# ContunityTestingRig.net
KiCad netlist of a schematic drawn in EAGLE
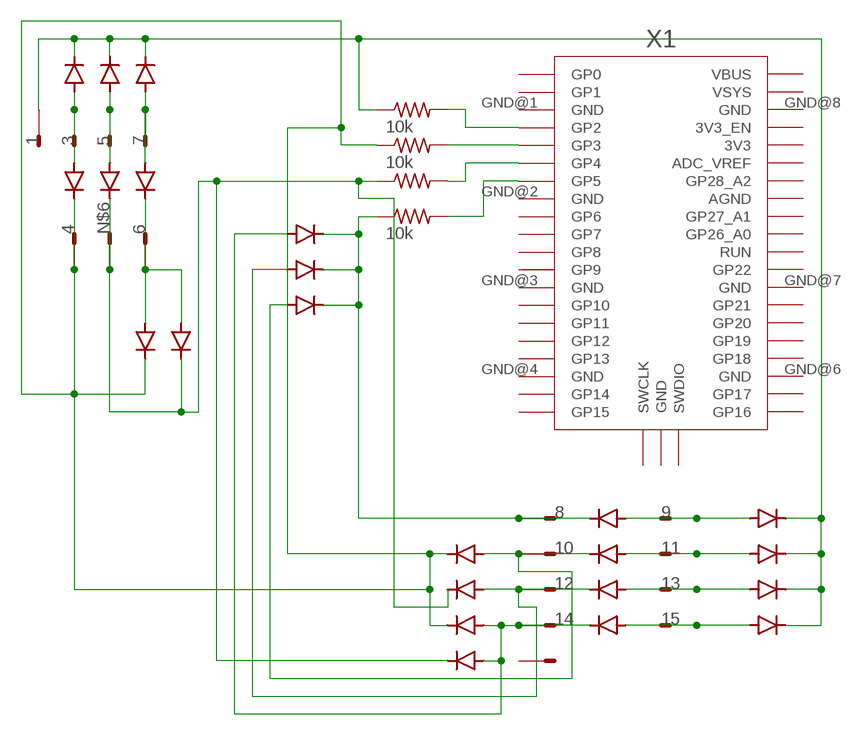
[diagram p0: schematic, sheet 1]

(export (version "E")
  (design (tool "Eeschema 10.0.6"))
  (components
    (comp (ref "D1")
      (value "SCHOTTKY")
      (footprint "eagle-import:MINI-SMA")
      (libsource (lib "eagle-import") (part "DIODE_SCHOTTKY_CDBM1100-G"))
    )
    (comp (ref "D2")
      (value "SCHOTTKY")
      (footprint "eagle-import:MINI-SMA")
      (libsource (lib "eagle-import") (part "DIODE_SCHOTTKY_CDBM1100-G"))
    )
    (comp (ref "D3")
      (value "SCHOTTKY")
      (footprint "eagle-import:MINI-SMA")
      (libsource (lib "eagle-import") (part "DIODE_SCHOTTKY_CDBM1100-G"))
    )
    (comp (ref "D4")
      (value "SCHOTTKY")
      (footprint "eagle-import:MINI-SMA")
      (libsource (lib "eagle-import") (part "DIODE_SCHOTTKY_CDBM1100-G"))
    )
    (comp (ref "D5")
      (value "SCHOTTKY")
      (footprint "eagle-import:MINI-SMA")
      (libsource (lib "eagle-import") (part "DIODE_SCHOTTKY_CDBM1100-G"))
    )
    (comp (ref "D6")
      (value "SCHOTTKY")
      (footprint "eagle-import:MINI-SMA")
      (libsource (lib "eagle-import") (part "DIODE_SCHOTTKY_CDBM1100-G"))
    )
    (comp (ref "D7")
      (value "SCHOTTKY")
      (footprint "eagle-import:MINI-SMA")
      (libsource (lib "eagle-import") (part "DIODE_SCHOTTKY_CDBM1100-G"))
    )
    (comp (ref "D8")
      (value "SCHOTTKY")
      (footprint "eagle-import:MINI-SMA")
      (libsource (lib "eagle-import") (part "DIODE_SCHOTTKY_CDBM1100-G"))
    )
    (comp (ref "D9")
      (value "SCHOTTKY")
      (footprint "eagle-import:MINI-SMA")
      (libsource (lib "eagle-import") (part "DIODE_SCHOTTKY_CDBM1100-G"))
    )
    (comp (ref "D10")
      (value "SCHOTTKY")
      (footprint "eagle-import:MINI-SMA")
      (libsource (lib "eagle-import") (part "DIODE_SCHOTTKY_CDBM1100-G"))
    )
    (comp (ref "D11")
      (value "SCHOTTKY")
      (footprint "eagle-import:MINI-SMA")
      (libsource (lib "eagle-import") (part "DIODE_SCHOTTKY_CDBM1100-G"))
    )
    (comp (ref "D12")
      (value "SCHOTTKY")
      (footprint "eagle-import:MINI-SMA")
      (libsource (lib "eagle-import") (part "DIODE_SCHOTTKY_CDBM1100-G"))
    )
    (comp (ref "D13")
      (value "SCHOTTKY")
      (footprint "eagle-import:MINI-SMA")
      (libsource (lib "eagle-import") (part "DIODE_SCHOTTKY_CDBM1100-G"))
    )
    (comp (ref "D14")
      (value "SCHOTTKY")
      (footprint "eagle-import:MINI-SMA")
      (libsource (lib "eagle-import") (part "DIODE_SCHOTTKY_CDBM1100-G"))
    )
    (comp (ref "D15")
      (value "SCHOTTKY")
      (footprint "eagle-import:MINI-SMA")
      (libsource (lib "eagle-import") (part "DIODE_SCHOTTKY_CDBM1100-G"))
    )
    (comp (ref "D16")
      (value "SCHOTTKY")
      (footprint "eagle-import:MINI-SMA")
      (libsource (lib "eagle-import") (part "DIODE_SCHOTTKY_CDBM1100-G"))
    )
    (comp (ref "D17")
      (value "SCHOTTKY")
      (footprint "eagle-import:MINI-SMA")
      (libsource (lib "eagle-import") (part "DIODE_SCHOTTKY_CDBM1100-G"))
    )
    (comp (ref "D18")
      (value "SCHOTTKY")
      (footprint "eagle-import:MINI-SMA")
      (libsource (lib "eagle-import") (part "DIODE_SCHOTTKY_CDBM1100-G"))
    )
    (comp (ref "D19")
      (value "SCHOTTKY")
      (footprint "eagle-import:MINI-SMA")
      (libsource (lib "eagle-import") (part "DIODE_SCHOTTKY_CDBM1100-G"))
    )
    (comp (ref "D20")
      (value "SCHOTTKY")
      (footprint "eagle-import:MINI-SMA")
      (libsource (lib "eagle-import") (part "DIODE_SCHOTTKY_CDBM1100-G"))
    )
    (comp (ref "D21")
      (value "SCHOTTKY")
      (footprint "eagle-import:MINI-SMA")
      (libsource (lib "eagle-import") (part "DIODE_SCHOTTKY_CDBM1100-G"))
    )
    (comp (ref "D22")
      (value "SCHOTTKY")
      (footprint "eagle-import:MINI-SMA")
      (libsource (lib "eagle-import") (part "DIODE_SCHOTTKY_CDBM1100-G"))
    )
    (comp (ref "D23")
      (value "SCHOTTKY")
      (footprint "eagle-import:MINI-SMA")
      (libsource (lib "eagle-import") (part "DIODE_SCHOTTKY_CDBM1100-G"))
    )
    (comp (ref "R1")
      (value "10k")
      (footprint "eagle-import:R1206FAB")
      (libsource (lib "eagle-import") (part "R1206FAB"))
    )
    (comp (ref "R2")
      (value "10k")
      (footprint "eagle-import:R1206FAB")
      (libsource (lib "eagle-import") (part "R1206FAB"))
    )
    (comp (ref "R3")
      (value "10k")
      (footprint "eagle-import:R1206FAB")
      (libsource (lib "eagle-import") (part "R1206FAB"))
    )
    (comp (ref "R4")
      (value "10k")
      (footprint "eagle-import:R1206FAB")
      (libsource (lib "eagle-import") (part "R1206FAB"))
    )
    (comp (ref "SV1")
      (value "16E")
      (footprint "eagle-import:16P")
      (libsource (lib "eagle-import") (part "16E"))
    )
    (comp (ref "X1")
      (value "RPI_PICO_IG-SMD")
      (footprint "eagle-import:RPI_PICO")
      (libsource (lib "eagle-import") (part "RPI_PICO_IG-SMD"))
    )
  )
  (nets
    (net (code "1") (name "/1") (class "Default")
      (node (ref "D1") (pin "KATHODE") (pinfunction "KATHODE_KATHODE") (pintype "bidirectional"))
      (node (ref "D13") (pin "KATHODE") (pinfunction "KATHODE_KATHODE") (pintype "bidirectional"))
      (node (ref "D14") (pin "KATHODE") (pinfunction "KATHODE_KATHODE") (pintype "bidirectional"))
      (node (ref "D15") (pin "KATHODE") (pinfunction "KATHODE_KATHODE") (pintype "bidirectional"))
      (node (ref "D16") (pin "KATHODE") (pinfunction "KATHODE_KATHODE") (pintype "bidirectional"))
      (node (ref "D2") (pin "KATHODE") (pinfunction "KATHODE_KATHODE") (pintype "bidirectional"))
      (node (ref "D3") (pin "KATHODE") (pinfunction "KATHODE_KATHODE") (pintype "bidirectional"))
      (node (ref "R1") (pin "1") (pinfunction "1_1") (pintype "passive"))
      (node (ref "SV1") (pin "1") (pinfunction "S_1") (pintype "passive"))
    )
    (net (code "2") (name "/3") (class "Default")
      (node (ref "D1") (pin "ANODE") (pinfunction "ANODE_ANODE") (pintype "bidirectional"))
      (node (ref "D4") (pin "ANODE") (pinfunction "ANODE_ANODE") (pintype "bidirectional"))
      (node (ref "SV1") (pin "3") (pinfunction "S_3") (pintype "passive"))
    )
    (net (code "3") (name "/4") (class "Default")
      (node (ref "D17") (pin "KATHODE") (pinfunction "KATHODE_KATHODE") (pintype "bidirectional"))
      (node (ref "D18") (pin "KATHODE") (pinfunction "KATHODE_KATHODE") (pintype "bidirectional"))
      (node (ref "D4") (pin "KATHODE") (pinfunction "KATHODE_KATHODE") (pintype "bidirectional"))
      (node (ref "D7") (pin "KATHODE") (pinfunction "KATHODE_KATHODE") (pintype "bidirectional"))
      (node (ref "R2") (pin "1") (pinfunction "1_1") (pintype "passive"))
      (node (ref "SV1") (pin "2") (pinfunction "S_2") (pintype "passive"))
    )
    (net (code "4") (name "/5") (class "Default")
      (node (ref "D2") (pin "ANODE") (pinfunction "ANODE_ANODE") (pintype "bidirectional"))
      (node (ref "D5") (pin "ANODE") (pinfunction "ANODE_ANODE") (pintype "bidirectional"))
      (node (ref "SV1") (pin "5") (pinfunction "S_5") (pintype "passive"))
    )
    (net (code "5") (name "/6") (class "Default")
      (node (ref "D6") (pin "KATHODE") (pinfunction "KATHODE_KATHODE") (pintype "bidirectional"))
      (node (ref "D7") (pin "ANODE") (pinfunction "ANODE_ANODE") (pintype "bidirectional"))
      (node (ref "D8") (pin "ANODE") (pinfunction "ANODE_ANODE") (pintype "bidirectional"))
      (node (ref "SV1") (pin "6") (pinfunction "S_6") (pintype "passive"))
    )
    (net (code "6") (name "/7") (class "Default")
      (node (ref "D3") (pin "ANODE") (pinfunction "ANODE_ANODE") (pintype "bidirectional"))
      (node (ref "D6") (pin "ANODE") (pinfunction "ANODE_ANODE") (pintype "bidirectional"))
      (node (ref "SV1") (pin "7") (pinfunction "S_7") (pintype "passive"))
    )
    (net (code "7") (name "/8") (class "Default")
      (node (ref "D21") (pin "KATHODE") (pinfunction "KATHODE_KATHODE") (pintype "bidirectional"))
      (node (ref "D22") (pin "KATHODE") (pinfunction "KATHODE_KATHODE") (pintype "bidirectional"))
      (node (ref "D23") (pin "KATHODE") (pinfunction "KATHODE_KATHODE") (pintype "bidirectional"))
      (node (ref "D9") (pin "KATHODE") (pinfunction "KATHODE_KATHODE") (pintype "bidirectional"))
      (node (ref "R4") (pin "1") (pinfunction "1_1") (pintype "passive"))
      (node (ref "SV1") (pin "8") (pinfunction "S_8") (pintype "passive"))
    )
    (net (code "8") (name "/9") (class "Default")
      (node (ref "D13") (pin "ANODE") (pinfunction "ANODE_ANODE") (pintype "bidirectional"))
      (node (ref "D9") (pin "ANODE") (pinfunction "ANODE_ANODE") (pintype "bidirectional"))
      (node (ref "SV1") (pin "9") (pinfunction "S_9") (pintype "passive"))
    )
    (net (code "9") (name "/10") (class "Default")
      (node (ref "D10") (pin "KATHODE") (pinfunction "KATHODE_KATHODE") (pintype "bidirectional"))
      (node (ref "D17") (pin "ANODE") (pinfunction "ANODE_ANODE") (pintype "bidirectional"))
      (node (ref "D23") (pin "ANODE") (pinfunction "ANODE_ANODE") (pintype "bidirectional"))
      (node (ref "SV1") (pin "10") (pinfunction "S_10") (pintype "passive"))
    )
    (net (code "10") (name "/11") (class "Default")
      (node (ref "D10") (pin "ANODE") (pinfunction "ANODE_ANODE") (pintype "bidirectional"))
      (node (ref "D14") (pin "ANODE") (pinfunction "ANODE_ANODE") (pintype "bidirectional"))
      (node (ref "SV1") (pin "11") (pinfunction "S_11") (pintype "passive"))
    )
    (net (code "11") (name "/12") (class "Default")
      (node (ref "D11") (pin "KATHODE") (pinfunction "KATHODE_KATHODE") (pintype "bidirectional"))
      (node (ref "D19") (pin "ANODE") (pinfunction "ANODE_ANODE") (pintype "bidirectional"))
      (node (ref "D22") (pin "ANODE") (pinfunction "ANODE_ANODE") (pintype "bidirectional"))
      (node (ref "SV1") (pin "12") (pinfunction "S_12") (pintype "passive"))
    )
    (net (code "12") (name "/13") (class "Default")
      (node (ref "D11") (pin "ANODE") (pinfunction "ANODE_ANODE") (pintype "bidirectional"))
      (node (ref "D15") (pin "ANODE") (pinfunction "ANODE_ANODE") (pintype "bidirectional"))
      (node (ref "SV1") (pin "13") (pinfunction "S_13") (pintype "passive"))
    )
    (net (code "13") (name "/14") (class "Default")
      (node (ref "D12") (pin "KATHODE") (pinfunction "KATHODE_KATHODE") (pintype "bidirectional"))
      (node (ref "D18") (pin "ANODE") (pinfunction "ANODE_ANODE") (pintype "bidirectional"))
      (node (ref "D20") (pin "ANODE") (pinfunction "ANODE_ANODE") (pintype "bidirectional"))
      (node (ref "D21") (pin "ANODE") (pinfunction "ANODE_ANODE") (pintype "bidirectional"))
      (node (ref "SV1") (pin "14") (pinfunction "S_14") (pintype "passive"))
    )
    (net (code "14") (name "/15") (class "Default")
      (node (ref "D12") (pin "ANODE") (pinfunction "ANODE_ANODE") (pintype "bidirectional"))
      (node (ref "D16") (pin "ANODE") (pinfunction "ANODE_ANODE") (pintype "bidirectional"))
      (node (ref "SV1") (pin "15") (pinfunction "S_15") (pintype "passive"))
    )
    (net (code "15") (name "/N$6") (class "Default")
      (node (ref "D19") (pin "KATHODE") (pinfunction "KATHODE_KATHODE") (pintype "bidirectional"))
      (node (ref "D20") (pin "KATHODE") (pinfunction "KATHODE_KATHODE") (pintype "bidirectional"))
      (node (ref "D5") (pin "KATHODE") (pinfunction "KATHODE_KATHODE") (pintype "bidirectional"))
      (node (ref "D8") (pin "KATHODE") (pinfunction "KATHODE_KATHODE") (pintype "bidirectional"))
      (node (ref "R3") (pin "1") (pinfunction "1_1") (pintype "passive"))
      (node (ref "SV1") (pin "4") (pinfunction "S_4") (pintype "passive"))
    )
    (net (code "16") (name "Net-(R1-Pad2)") (class "Default")
      (node (ref "R1") (pin "2") (pinfunction "2_2") (pintype "passive"))
      (node (ref "X1") (pin "GP2") (pinfunction "GP2_GP2") (pintype "bidirectional"))
    )
    (net (code "17") (name "Net-(R2-Pad2)") (class "Default")
      (node (ref "R2") (pin "2") (pinfunction "2_2") (pintype "passive"))
      (node (ref "X1") (pin "GP3") (pinfunction "GP3_GP3") (pintype "bidirectional"))
    )
    (net (code "18") (name "Net-(R3-Pad2)") (class "Default")
      (node (ref "R3") (pin "2") (pinfunction "2_2") (pintype "passive"))
      (node (ref "X1") (pin "GP4") (pinfunction "GP4_GP4") (pintype "bidirectional"))
    )
    (net (code "19") (name "Net-(R4-Pad2)") (class "Default")
      (node (ref "R4") (pin "2") (pinfunction "2_2") (pintype "passive"))
      (node (ref "X1") (pin "GP5") (pinfunction "GP5_GP5") (pintype "bidirectional"))
    )
    (net (code "20") (name "unconnected-(SV1H-S-Pad16)") (class "Default")
      (node (ref "SV1") (pin "16") (pinfunction "S_16") (pintype "passive"))
    )
    (net (code "21") (name "unconnected-(X1-GND-PadGND@1)") (class "Default")
      (node (ref "X1") (pin "GND@1") (pinfunction "GND_GND@1") (pintype "bidirectional"))
    )
    (net (code "22") (name "unconnected-(X1-GND-PadGND@2)") (class "Default")
      (node (ref "X1") (pin "GND@2") (pinfunction "GND_GND@2") (pintype "bidirectional"))
    )
    (net (code "23") (name "unconnected-(X1-GND-PadGND@3)") (class "Default")
      (node (ref "X1") (pin "GND@3") (pinfunction "GND_GND@3") (pintype "bidirectional"))
    )
    (net (code "24") (name "unconnected-(X1-GND-PadGND@4)") (class "Default")
      (node (ref "X1") (pin "GND@4") (pinfunction "GND_GND@4") (pintype "bidirectional"))
    )
    (net (code "25") (name "unconnected-(X1-GND-PadGND@5)") (class "Default")
      (node (ref "X1") (pin "GND@5") (pinfunction "GND_GND@5") (pintype "bidirectional"))
    )
    (net (code "26") (name "unconnected-(X1-GND-PadGND@6)") (class "Default")
      (node (ref "X1") (pin "GND@6") (pinfunction "GND_GND@6") (pintype "bidirectional"))
    )
    (net (code "27") (name "unconnected-(X1-GND-PadGND@7)") (class "Default")
      (node (ref "X1") (pin "GND@7") (pinfunction "GND_GND@7") (pintype "bidirectional"))
    )
    (net (code "28") (name "unconnected-(X1-GND-PadGND@8)") (class "Default")
      (node (ref "X1") (pin "GND@8") (pinfunction "GND_GND@8") (pintype "bidirectional"))
    )
    (net (code "29") (name "unconnected-(X1-Pad3V3)") (class "Default")
      (node (ref "X1") (pin "3V3") (pinfunction "3V3_3V3") (pintype "bidirectional"))
    )
    (net (code "30") (name "unconnected-(X1-Pad3V3_EN)") (class "Default")
      (node (ref "X1") (pin "3V3_EN") (pinfunction "3V3_EN_3V3_EN") (pintype "bidirectional"))
    )
    (net (code "31") (name "unconnected-(X1-PadADC_VREF)") (class "Default")
      (node (ref "X1") (pin "ADC_VREF") (pinfunction "ADC_VREF_ADC_VREF") (pintype "bidirectional"))
    )
    (net (code "32") (name "unconnected-(X1-PadAGND)") (class "Default")
      (node (ref "X1") (pin "AGND") (pinfunction "AGND_AGND") (pintype "bidirectional"))
    )
    (net (code "33") (name "unconnected-(X1-PadGP0)") (class "Default")
      (node (ref "X1") (pin "GP0") (pinfunction "GP0_GP0") (pintype "bidirectional"))
    )
    (net (code "34") (name "unconnected-(X1-PadGP1)") (class "Default")
      (node (ref "X1") (pin "GP1") (pinfunction "GP1_GP1") (pintype "bidirectional"))
    )
    (net (code "35") (name "unconnected-(X1-PadGP6)") (class "Default")
      (node (ref "X1") (pin "GP6") (pinfunction "GP6_GP6") (pintype "bidirectional"))
    )
    (net (code "36") (name "unconnected-(X1-PadGP7)") (class "Default")
      (node (ref "X1") (pin "GP7") (pinfunction "GP7_GP7") (pintype "bidirectional"))
    )
    (net (code "37") (name "unconnected-(X1-PadGP8)") (class "Default")
      (node (ref "X1") (pin "GP8") (pinfunction "GP8_GP8") (pintype "bidirectional"))
    )
    (net (code "38") (name "unconnected-(X1-PadGP9)") (class "Default")
      (node (ref "X1") (pin "GP9") (pinfunction "GP9_GP9") (pintype "bidirectional"))
    )
    (net (code "39") (name "unconnected-(X1-PadGP10)") (class "Default")
      (node (ref "X1") (pin "GP10") (pinfunction "GP10_GP10") (pintype "bidirectional"))
    )
    (net (code "40") (name "unconnected-(X1-PadGP11)") (class "Default")
      (node (ref "X1") (pin "GP11") (pinfunction "GP11_GP11") (pintype "bidirectional"))
    )
    (net (code "41") (name "unconnected-(X1-PadGP12)") (class "Default")
      (node (ref "X1") (pin "GP12") (pinfunction "GP12_GP12") (pintype "bidirectional"))
    )
    (net (code "42") (name "unconnected-(X1-PadGP13)") (class "Default")
      (node (ref "X1") (pin "GP13") (pinfunction "GP13_GP13") (pintype "bidirectional"))
    )
    (net (code "43") (name "unconnected-(X1-PadGP14)") (class "Default")
      (node (ref "X1") (pin "GP14") (pinfunction "GP14_GP14") (pintype "bidirectional"))
    )
    (net (code "44") (name "unconnected-(X1-PadGP15)") (class "Default")
      (node (ref "X1") (pin "GP15") (pinfunction "GP15_GP15") (pintype "bidirectional"))
    )
    (net (code "45") (name "unconnected-(X1-PadGP16)") (class "Default")
      (node (ref "X1") (pin "GP16") (pinfunction "GP16_GP16") (pintype "bidirectional"))
    )
    (net (code "46") (name "unconnected-(X1-PadGP17)") (class "Default")
      (node (ref "X1") (pin "GP17") (pinfunction "GP17_GP17") (pintype "bidirectional"))
    )
    (net (code "47") (name "unconnected-(X1-PadGP18)") (class "Default")
      (node (ref "X1") (pin "GP18") (pinfunction "GP18_GP18") (pintype "bidirectional"))
    )
    (net (code "48") (name "unconnected-(X1-PadGP19)") (class "Default")
      (node (ref "X1") (pin "GP19") (pinfunction "GP19_GP19") (pintype "bidirectional"))
    )
    (net (code "49") (name "unconnected-(X1-PadGP20)") (class "Default")
      (node (ref "X1") (pin "GP20") (pinfunction "GP20_GP20") (pintype "bidirectional"))
    )
    (net (code "50") (name "unconnected-(X1-PadGP21)") (class "Default")
      (node (ref "X1") (pin "GP21") (pinfunction "GP21_GP21") (pintype "bidirectional"))
    )
    (net (code "51") (name "unconnected-(X1-PadGP22)") (class "Default")
      (node (ref "X1") (pin "GP22") (pinfunction "GP22_GP22") (pintype "bidirectional"))
    )
    (net (code "52") (name "unconnected-(X1-PadGP26_A0)") (class "Default")
      (node (ref "X1") (pin "GP26_A0") (pinfunction "GP26_A0_GP26_A0") (pintype "bidirectional"))
    )
    (net (code "53") (name "unconnected-(X1-PadGP27_A1)") (class "Default")
      (node (ref "X1") (pin "GP27_A1") (pinfunction "GP27_A1_GP27_A1") (pintype "bidirectional"))
    )
    (net (code "54") (name "unconnected-(X1-PadGP28_A2)") (class "Default")
      (node (ref "X1") (pin "GP28_A2") (pinfunction "GP28_A2_GP28_A2") (pintype "bidirectional"))
    )
    (net (code "55") (name "unconnected-(X1-PadRUN)") (class "Default")
      (node (ref "X1") (pin "RUN") (pinfunction "RUN_RUN") (pintype "bidirectional"))
    )
    (net (code "56") (name "unconnected-(X1-PadSWCLK)") (class "Default")
      (node (ref "X1") (pin "SWCLK") (pinfunction "SWCLK_SWCLK") (pintype "bidirectional"))
    )
    (net (code "57") (name "unconnected-(X1-PadSWDIO)") (class "Default")
      (node (ref "X1") (pin "SWDIO") (pinfunction "SWDIO_SWDIO") (pintype "bidirectional"))
    )
    (net (code "58") (name "unconnected-(X1-PadVBUS)") (class "Default")
      (node (ref "X1") (pin "VBUS") (pinfunction "VBUS_VBUS") (pintype "bidirectional"))
    )
    (net (code "59") (name "unconnected-(X1-PadVSYS)") (class "Default")
      (node (ref "X1") (pin "VSYS") (pinfunction "VSYS_VSYS") (pintype "bidirectional"))
    )
  )
)
